# Sensorboard.net
KiCad netlist of a schematic drawn in Altium Designer
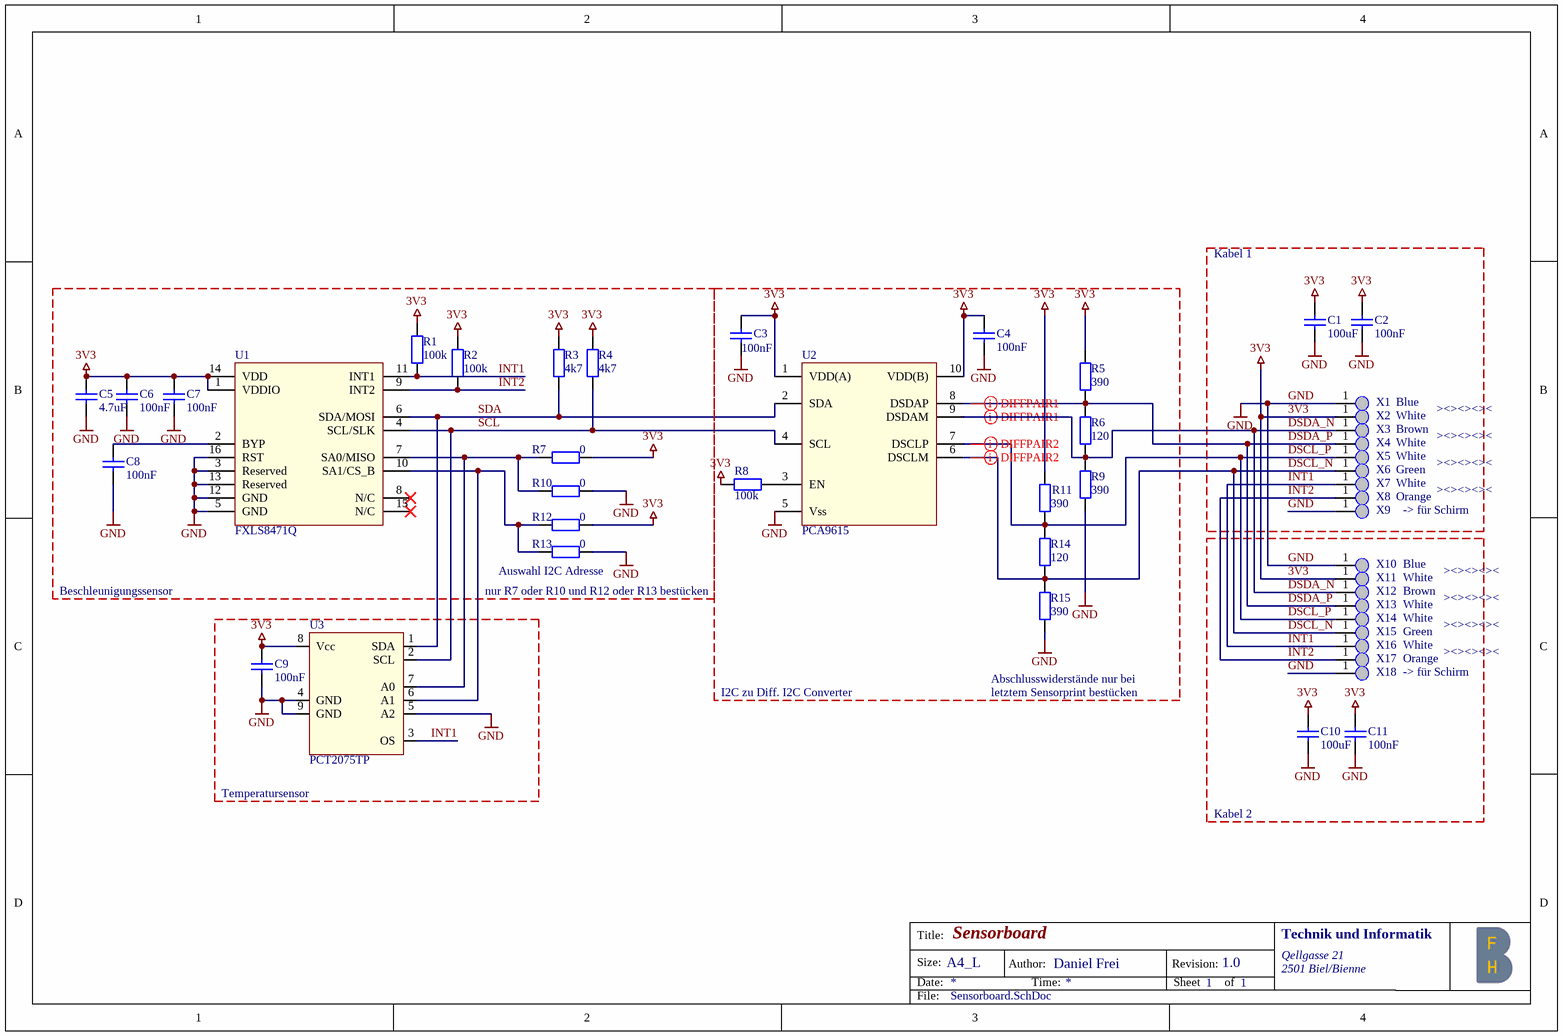
[diagram p0: Sensorboard.SchDoc]

(export (version "E")
  (design (tool "Eeschema 10.0.6"))
  (components
    (comp (ref "C1")
      (value "100uF")
      (footprint "RC_SMD_3D:CAPC3225[1210]X120")
      (description "Capacitor")
      (fields
        (field (name "MANUFACTURER") "Murata")
        (field (name "MANUFACTURER PART NUMBER") "GRM32ER61A107ME20L")
        (field (name "MODIFIED_BY") "BEP1")
      )
      (libsource (lib "RC_SMD_3D") (part "C"))
    )
    (comp (ref "C2")
      (value "100nF")
      (footprint "RC_SMD_3D:CAPC1005[0402]X50")
      (description "Capacitor")
      (fields (field (name "MODIFIED_BY") "BEP1"))
      (libsource (lib "RC_SMD_3D") (part "C"))
    )
    (comp (ref "C3")
      (value "100nF")
      (footprint "RC_SMD_3D:CAPC1005[0402]X50")
      (description "Capacitor")
      (fields (field (name "MODIFIED_BY") "BEP1"))
      (libsource (lib "RC_SMD_3D") (part "C"))
    )
    (comp (ref "C4")
      (value "100nF")
      (footprint "RC_SMD_3D:CAPC1005[0402]X50")
      (description "Capacitor")
      (fields (field (name "MODIFIED_BY") "BEP1"))
      (libsource (lib "RC_SMD_3D") (part "C"))
    )
    (comp (ref "C5")
      (value "4.7uF")
      (footprint "RC_SMD_3D:CAPC1608[0603]X80")
      (description "Capacitor")
      (fields
        (field (name "VOLTAGE") "10V")
        (field (name "MANUFACTURER") "Murata")
        (field (name "MODIFIED_BY") "BEP1")
      )
      (libsource (lib "RC_SMD_3D") (part "C"))
    )
    (comp (ref "C6")
      (value "100nF")
      (footprint "RC_SMD_3D:CAPC1005[0402]X50")
      (description "Capacitor")
      (fields (field (name "MODIFIED_BY") "BEP1"))
      (libsource (lib "RC_SMD_3D") (part "C"))
    )
    (comp (ref "C7")
      (value "100nF")
      (footprint "RC_SMD_3D:CAPC1005[0402]X50")
      (description "Capacitor")
      (fields (field (name "MODIFIED_BY") "BEP1"))
      (libsource (lib "RC_SMD_3D") (part "C"))
    )
    (comp (ref "C8")
      (value "100nF")
      (footprint "RC_SMD_3D:CAPC1005[0402]X50")
      (description "Capacitor")
      (fields (field (name "MODIFIED_BY") "BEP1"))
      (libsource (lib "RC_SMD_3D") (part "C"))
    )
    (comp (ref "C9")
      (value "100nF")
      (footprint "RC_SMD_3D:CAPC1005[0402]X50")
      (description "Capacitor")
      (fields (field (name "MODIFIED_BY") "BEP1"))
      (libsource (lib "RC_SMD_3D") (part "C"))
    )
    (comp (ref "C10")
      (value "100uF")
      (footprint "RC_SMD_3D:CAPC3225[1210]X120")
      (description "Capacitor")
      (fields
        (field (name "MANUFACTURER") "Murata")
        (field (name "MANUFACTURER PART NUMBER") "GRM32ER61A107ME20L")
        (field (name "MODIFIED_BY") "BEP1")
      )
      (libsource (lib "RC_SMD_3D") (part "C"))
    )
    (comp (ref "C11")
      (value "100nF")
      (footprint "RC_SMD_3D:CAPC1005[0402]X50")
      (description "Capacitor")
      (fields (field (name "MODIFIED_BY") "BEP1"))
      (libsource (lib "RC_SMD_3D") (part "C"))
    )
    (comp (ref "R1")
      (value "100k")
      (footprint "RC_SMD_3D:RESC1005[0402]X35")
      (description "Resistor")
      (fields (field (name "MODIFIED_BY") "BEP1"))
      (libsource (lib "RC_SMD_3D") (part "R"))
    )
    (comp (ref "R2")
      (value "100k")
      (footprint "RC_SMD_3D:RESC1005[0402]X35")
      (description "Resistor")
      (fields (field (name "MODIFIED_BY") "BEP1"))
      (libsource (lib "RC_SMD_3D") (part "R"))
    )
    (comp (ref "R3")
      (value "4k7")
      (footprint "RC_SMD_3D:RESC1005[0402]X35")
      (description "Resistor")
      (fields (field (name "MODIFIED_BY") "BEP1"))
      (libsource (lib "RC_SMD_3D") (part "R"))
    )
    (comp (ref "R4")
      (value "4k7")
      (footprint "RC_SMD_3D:RESC1005[0402]X35")
      (description "Resistor")
      (fields (field (name "MODIFIED_BY") "BEP1"))
      (libsource (lib "RC_SMD_3D") (part "R"))
    )
    (comp (ref "R5")
      (value "390")
      (footprint "RC_SMD_3D:RESC1005[0402]X35")
      (description "Resistor")
      (fields (field (name "MODIFIED_BY") "BEP1"))
      (libsource (lib "RC_SMD_3D") (part "R"))
    )
    (comp (ref "R6")
      (value "120")
      (footprint "RC_SMD_3D:RESC1005[0402]X35")
      (description "Resistor")
      (fields (field (name "MODIFIED_BY") "BEP1"))
      (libsource (lib "RC_SMD_3D") (part "R"))
    )
    (comp (ref "R7")
      (value "0")
      (footprint "RC_SMD_3D:RESC1005[0402]X35")
      (description "Resistor")
      (fields
        (field (name "MANUFACTURER") "Panasonic")
        (field (name "MANUFACTURER PART NUMBER") "ERJ-2GE0R00X")
        (field (name "MODIFIED_BY") "BEP1")
      )
      (libsource (lib "") (part "R_1"))
    )
    (comp (ref "R8")
      (value "100k")
      (footprint "RC_SMD_3D:RESC1005[0402]X35")
      (description "Resistor")
      (fields (field (name "MODIFIED_BY") "BEP1"))
      (libsource (lib "") (part "R_1"))
    )
    (comp (ref "R9")
      (value "390")
      (footprint "RC_SMD_3D:RESC1005[0402]X35")
      (description "Resistor")
      (fields (field (name "MODIFIED_BY") "BEP1"))
      (libsource (lib "RC_SMD_3D") (part "R"))
    )
    (comp (ref "R10")
      (value "0")
      (footprint "RC_SMD_3D:RESC1005[0402]X35")
      (description "Resistor")
      (fields
        (field (name "MANUFACTURER") "Panasonic")
        (field (name "MANUFACTURER PART NUMBER") "ERJ-2GE0R00X")
        (field (name "MODIFIED_BY") "BEP1")
      )
      (libsource (lib "") (part "R_1"))
    )
    (comp (ref "R11")
      (value "390")
      (footprint "RC_SMD_3D:RESC1005[0402]X35")
      (description "Resistor")
      (fields (field (name "MODIFIED_BY") "BEP1"))
      (libsource (lib "RC_SMD_3D") (part "R"))
    )
    (comp (ref "R12")
      (value "0")
      (footprint "RC_SMD_3D:RESC1005[0402]X35")
      (description "Resistor")
      (fields
        (field (name "MANUFACTURER") "Panasonic")
        (field (name "MANUFACTURER PART NUMBER") "ERJ-2GE0R00X")
        (field (name "MODIFIED_BY") "BEP1")
      )
      (libsource (lib "") (part "R_1"))
    )
    (comp (ref "R13")
      (value "0")
      (footprint "RC_SMD_3D:RESC1005[0402]X35")
      (description "Resistor")
      (fields
        (field (name "MANUFACTURER") "Panasonic")
        (field (name "MANUFACTURER PART NUMBER") "ERJ-2GE0R00X")
        (field (name "MODIFIED_BY") "BEP1")
      )
      (libsource (lib "") (part "R_1"))
    )
    (comp (ref "R14")
      (value "120")
      (footprint "RC_SMD_3D:RESC1005[0402]X35")
      (description "Resistor")
      (fields (field (name "MODIFIED_BY") "BEP1"))
      (libsource (lib "RC_SMD_3D") (part "R"))
    )
    (comp (ref "R15")
      (value "390")
      (footprint "RC_SMD_3D:RESC1005[0402]X35")
      (description "Resistor")
      (fields (field (name "MODIFIED_BY") "BEP1"))
      (libsource (lib "RC_SMD_3D") (part "R"))
    )
    (comp (ref "U1")
      (value "FXLS8471Q")
      (footprint "16 LEAD QFN")
      (description "3-Axis,  Linear Accelerometer")
      (fields (field (name "MANUFACTURER PART NUMBER") "FXLS8471QR1") (field (name "MANUFACTURER") "NXP"))
      (libsource (lib "Sensorboard_Library") (part "FXLS8471Q"))
    )
    (comp (ref "U2")
      (value "PCA9615")
      (footprint "TSSOP10")
      (description "differential I2C-bus buffer")
      (fields (field (name "MANUFACTURER PART NUMBER") "PCA9615DPJ") (field (name "MANUFACTURER") "NXP"))
      (libsource (lib "Sensorboard_Library") (part "PCA9615"))
    )
    (comp (ref "U3")
      (value "PCT2075TP")
      (footprint "HWSON8")
      (description "Temperature_Sensor")
      (fields (field (name "MANUFACTURER") "NXP") (field (name "MANUFACTURER PART NUMBER") "PCT2075TP,147"))
      (libsource (lib "Sensorboard_Library") (part "PCT2075TP"))
    )
    (comp (ref "X1")
      (value "Loch")
      (footprint "Loch")
      (description "Loch in Print um Kabel einzulöten")
      (libsource (lib "Sensorboard_Library") (part "Loch"))
    )
    (comp (ref "X2")
      (value "Loch")
      (footprint "Loch")
      (description "Loch in Print um Kabel einzulöten")
      (libsource (lib "Sensorboard_Library") (part "Loch"))
    )
    (comp (ref "X3")
      (value "Loch")
      (footprint "Loch")
      (description "Loch in Print um Kabel einzulöten")
      (libsource (lib "Sensorboard_Library") (part "Loch"))
    )
    (comp (ref "X4")
      (value "Loch")
      (footprint "Loch")
      (description "Loch in Print um Kabel einzulöten")
      (libsource (lib "Sensorboard_Library") (part "Loch"))
    )
    (comp (ref "X5")
      (value "Loch")
      (footprint "Loch")
      (description "Loch in Print um Kabel einzulöten")
      (libsource (lib "Sensorboard_Library") (part "Loch"))
    )
    (comp (ref "X6")
      (value "Loch")
      (footprint "Loch")
      (description "Loch in Print um Kabel einzulöten")
      (libsource (lib "Sensorboard_Library") (part "Loch"))
    )
    (comp (ref "X7")
      (value "Loch")
      (footprint "Loch")
      (description "Loch in Print um Kabel einzulöten")
      (libsource (lib "Sensorboard_Library") (part "Loch"))
    )
    (comp (ref "X8")
      (value "Loch")
      (footprint "Loch")
      (description "Loch in Print um Kabel einzulöten")
      (libsource (lib "Sensorboard_Library") (part "Loch"))
    )
    (comp (ref "X9")
      (value "Loch")
      (footprint "Loch _gross")
      (description "Loch in Print um Kabel einzulöten")
      (libsource (lib "Sensorboard_Library") (part "Loch"))
    )
    (comp (ref "X10")
      (value "Loch")
      (footprint "Loch")
      (description "Loch in Print um Kabel einzulöten")
      (libsource (lib "Sensorboard_Library") (part "Loch"))
    )
    (comp (ref "X11")
      (value "Loch")
      (footprint "Loch")
      (description "Loch in Print um Kabel einzulöten")
      (libsource (lib "Sensorboard_Library") (part "Loch"))
    )
    (comp (ref "X12")
      (value "Loch")
      (footprint "Loch")
      (description "Loch in Print um Kabel einzulöten")
      (libsource (lib "Sensorboard_Library") (part "Loch"))
    )
    (comp (ref "X13")
      (value "Loch")
      (footprint "Loch")
      (description "Loch in Print um Kabel einzulöten")
      (libsource (lib "Sensorboard_Library") (part "Loch"))
    )
    (comp (ref "X14")
      (value "Loch")
      (footprint "Loch")
      (description "Loch in Print um Kabel einzulöten")
      (libsource (lib "Sensorboard_Library") (part "Loch"))
    )
    (comp (ref "X15")
      (value "Loch")
      (footprint "Loch")
      (description "Loch in Print um Kabel einzulöten")
      (libsource (lib "Sensorboard_Library") (part "Loch"))
    )
    (comp (ref "X16")
      (value "Loch")
      (footprint "Loch")
      (description "Loch in Print um Kabel einzulöten")
      (libsource (lib "Sensorboard_Library") (part "Loch"))
    )
    (comp (ref "X17")
      (value "Loch")
      (footprint "Loch")
      (description "Loch in Print um Kabel einzulöten")
      (libsource (lib "Sensorboard_Library") (part "Loch"))
    )
    (comp (ref "X18")
      (value "Loch")
      (footprint "Loch _gross")
      (description "Loch in Print um Kabel einzulöten")
      (libsource (lib "Sensorboard_Library") (part "Loch"))
    )
  )
  (nets
    (net (code "1") (name "/DSCL_N") (class "Default")
      (node (ref "R14") (pin "1") (pintype "passive"))
      (node (ref "R15") (pin "2") (pintype "passive"))
      (node (ref "U2") (pin "6") (pinfunction "DSCLM_6") (pintype "passive"))
      (node (ref "X15") (pin "1") (pinfunction "1_1") (pintype "passive"))
      (node (ref "X6") (pin "1") (pinfunction "1_1") (pintype "passive"))
    )
    (net (code "2") (name "/DSCL_P") (class "Default")
      (node (ref "R11") (pin "1") (pintype "passive"))
      (node (ref "R14") (pin "2") (pintype "passive"))
      (node (ref "U2") (pin "7") (pinfunction "DSCLP_7") (pintype "passive"))
      (node (ref "X14") (pin "1") (pinfunction "1_1") (pintype "passive"))
      (node (ref "X5") (pin "1") (pinfunction "1_1") (pintype "passive"))
    )
    (net (code "3") (name "/DSDA_N") (class "Default")
      (node (ref "R6") (pin "1") (pintype "passive"))
      (node (ref "R9") (pin "2") (pintype "passive"))
      (node (ref "U2") (pin "9") (pinfunction "DSDAM_9") (pintype "passive"))
      (node (ref "X12") (pin "1") (pinfunction "1_1") (pintype "passive"))
      (node (ref "X3") (pin "1") (pinfunction "1_1") (pintype "passive"))
    )
    (net (code "4") (name "/DSDA_P") (class "Default")
      (node (ref "R5") (pin "1") (pintype "passive"))
      (node (ref "R6") (pin "2") (pintype "passive"))
      (node (ref "U2") (pin "8") (pinfunction "DSDAP_8") (pintype "passive"))
      (node (ref "X13") (pin "1") (pinfunction "1_1") (pintype "passive"))
      (node (ref "X4") (pin "1") (pinfunction "1_1") (pintype "passive"))
    )
    (net (code "5") (name "/INT1") (class "Default")
      (node (ref "R1") (pin "1") (pintype "passive"))
      (node (ref "U1") (pin "11") (pinfunction "INT1_11") (pintype "passive"))
      (node (ref "U3") (pin "3") (pinfunction "OS_3") (pintype "passive"))
      (node (ref "X16") (pin "1") (pinfunction "1_1") (pintype "passive"))
      (node (ref "X7") (pin "1") (pinfunction "1_1") (pintype "passive"))
    )
    (net (code "6") (name "/INT2") (class "Default")
      (node (ref "R2") (pin "1") (pintype "passive"))
      (node (ref "U1") (pin "9") (pinfunction "INT2_9") (pintype "passive"))
      (node (ref "X17") (pin "1") (pinfunction "1_1") (pintype "passive"))
      (node (ref "X8") (pin "1") (pinfunction "1_1") (pintype "passive"))
    )
    (net (code "7") (name "/SCL") (class "Default")
      (node (ref "R4") (pin "1") (pintype "passive"))
      (node (ref "U1") (pin "4") (pinfunction "SCL/SLK_4") (pintype "passive"))
      (node (ref "U2") (pin "4") (pinfunction "SCL_4") (pintype "passive"))
      (node (ref "U3") (pin "2") (pinfunction "SCL_2") (pintype "passive"))
    )
    (net (code "8") (name "/SDA") (class "Default")
      (node (ref "R3") (pin "1") (pintype "passive"))
      (node (ref "U1") (pin "6") (pinfunction "SDA/MOSI_6") (pintype "passive"))
      (node (ref "U2") (pin "2") (pinfunction "SDA_2") (pintype "passive"))
      (node (ref "U3") (pin "1") (pinfunction "SDA_1") (pintype "passive"))
    )
    (net (code "9") (name "3V3") (class "Default")
      (node (ref "C1") (pin "2") (pintype "passive"))
      (node (ref "C10") (pin "2") (pintype "passive"))
      (node (ref "C11") (pin "2") (pintype "passive"))
      (node (ref "C2") (pin "2") (pintype "passive"))
      (node (ref "C3") (pin "2") (pintype "passive"))
      (node (ref "C4") (pin "2") (pintype "passive"))
      (node (ref "C5") (pin "2") (pintype "passive"))
      (node (ref "C6") (pin "2") (pintype "passive"))
      (node (ref "C7") (pin "2") (pintype "passive"))
      (node (ref "C9") (pin "2") (pintype "passive"))
      (node (ref "R1") (pin "2") (pintype "passive"))
      (node (ref "R11") (pin "2") (pintype "passive"))
      (node (ref "R12") (pin "2") (pintype "passive"))
      (node (ref "R2") (pin "2") (pintype "passive"))
      (node (ref "R3") (pin "2") (pintype "passive"))
      (node (ref "R4") (pin "2") (pintype "passive"))
      (node (ref "R5") (pin "2") (pintype "passive"))
      (node (ref "R7") (pin "2") (pintype "passive"))
      (node (ref "R8") (pin "1") (pintype "passive"))
      (node (ref "U1") (pin "1") (pinfunction "VDDIO_1") (pintype "passive"))
      (node (ref "U1") (pin "14") (pinfunction "VDD_14") (pintype "passive"))
      (node (ref "U2") (pin "1") (pinfunction "VDD(A)_1") (pintype "passive"))
      (node (ref "U2") (pin "10") (pinfunction "VDD(B)_10") (pintype "passive"))
      (node (ref "U3") (pin "8") (pinfunction "Vcc_8") (pintype "passive"))
      (node (ref "X11") (pin "1") (pinfunction "1_1") (pintype "passive"))
      (node (ref "X2") (pin "1") (pinfunction "1_1") (pintype "passive"))
    )
    (net (code "10") (name "GND") (class "Default")
      (node (ref "C1") (pin "1") (pintype "passive"))
      (node (ref "C10") (pin "1") (pintype "passive"))
      (node (ref "C11") (pin "1") (pintype "passive"))
      (node (ref "C2") (pin "1") (pintype "passive"))
      (node (ref "C3") (pin "1") (pintype "passive"))
      (node (ref "C4") (pin "1") (pintype "passive"))
      (node (ref "C5") (pin "1") (pintype "passive"))
      (node (ref "C6") (pin "1") (pintype "passive"))
      (node (ref "C7") (pin "1") (pintype "passive"))
      (node (ref "C8") (pin "1") (pintype "passive"))
      (node (ref "C9") (pin "1") (pintype "passive"))
      (node (ref "R10") (pin "2") (pintype "passive"))
      (node (ref "R13") (pin "2") (pintype "passive"))
      (node (ref "R15") (pin "1") (pintype "passive"))
      (node (ref "R9") (pin "1") (pintype "passive"))
      (node (ref "U1") (pin "12") (pinfunction "GND_12") (pintype "passive"))
      (node (ref "U1") (pin "13") (pinfunction "Reserved_13") (pintype "passive"))
      (node (ref "U1") (pin "16") (pinfunction "RST_16") (pintype "passive"))
      (node (ref "U1") (pin "3") (pinfunction "Reserved_3") (pintype "passive"))
      (node (ref "U1") (pin "5") (pinfunction "GND_5") (pintype "passive"))
      (node (ref "U2") (pin "5") (pinfunction "Vss_5") (pintype "passive"))
      (node (ref "U3") (pin "4") (pinfunction "GND_4") (pintype "passive"))
      (node (ref "U3") (pin "5") (pinfunction "A2_5") (pintype "passive"))
      (node (ref "U3") (pin "9") (pinfunction "GND_9") (pintype "passive"))
      (node (ref "X1") (pin "1") (pinfunction "1_1") (pintype "passive"))
      (node (ref "X10") (pin "1") (pinfunction "1_1") (pintype "passive"))
      (node (ref "X18") (pin "1") (pinfunction "1_1") (pintype "passive"))
      (node (ref "X9") (pin "1") (pinfunction "1_1") (pintype "passive"))
    )
    (net (code "11") (name "Net-(U1-BYP)") (class "Default")
      (node (ref "C8") (pin "2") (pintype "passive"))
      (node (ref "U1") (pin "2") (pinfunction "BYP_2") (pintype "passive"))
    )
    (net (code "12") (name "Net-(U1-SA0{slash}MISO)") (class "Default")
      (node (ref "R10") (pin "1") (pintype "passive"))
      (node (ref "R7") (pin "1") (pintype "passive"))
      (node (ref "U1") (pin "7") (pinfunction "SA0/MISO_7") (pintype "passive"))
      (node (ref "U3") (pin "7") (pinfunction "A0_7") (pintype "passive"))
    )
    (net (code "13") (name "Net-(U1-SA1{slash}CS_B)") (class "Default")
      (node (ref "R12") (pin "1") (pintype "passive"))
      (node (ref "R13") (pin "1") (pintype "passive"))
      (node (ref "U1") (pin "10") (pinfunction "SA1/CS_B_10") (pintype "passive"))
      (node (ref "U3") (pin "6") (pinfunction "A1_6") (pintype "passive"))
    )
    (net (code "14") (name "Net-(U2-EN)") (class "Default")
      (node (ref "R8") (pin "2") (pintype "passive"))
      (node (ref "U2") (pin "3") (pinfunction "EN_3") (pintype "passive"))
    )
    (net (code "15") (name "unconnected-(U1-N{slash}C-Pad8)") (class "Default")
      (node (ref "U1") (pin "8") (pinfunction "N/C_8") (pintype "passive+no_connect"))
    )
    (net (code "16") (name "unconnected-(U1-N{slash}C-Pad15)") (class "Default")
      (node (ref "U1") (pin "15") (pinfunction "N/C_15") (pintype "passive+no_connect"))
    )
  )
)
